# ESP8266_BREAKOUT.net
KiCad netlist of a schematic drawn in EAGLE
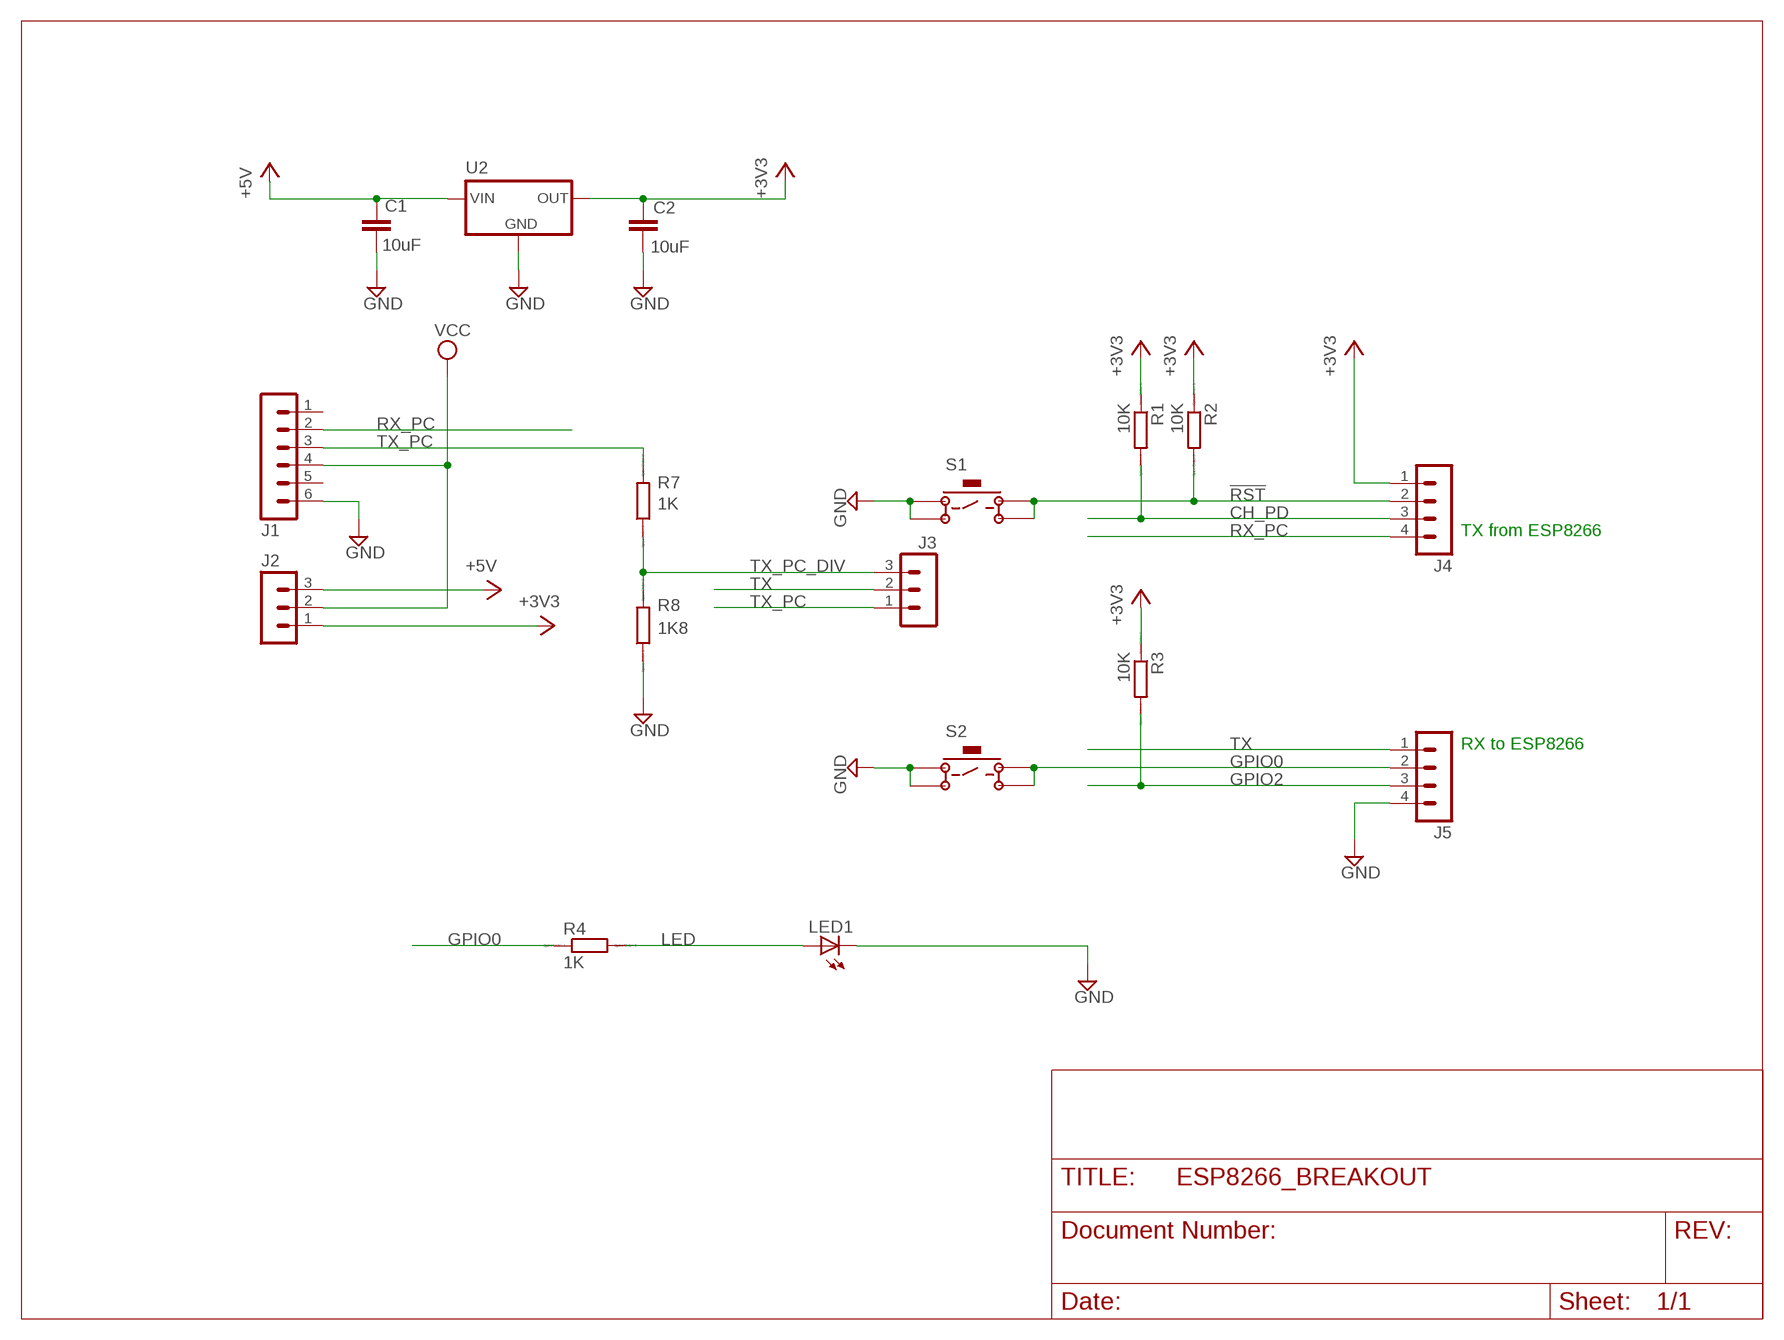
[diagram p0: schematic, sheet 1]

(export (version "E")
  (design (tool "Eeschema 10.0.6"))
  (components
    (comp (ref "C1")
      (value "10uF")
      (footprint "eagle-import:C5B2.5")
      (libsource (lib "eagle-import") (part "C5/2.5"))
    )
    (comp (ref "C2")
      (value "10uF")
      (footprint "eagle-import:C5B2.5")
      (libsource (lib "eagle-import") (part "C5/2.5"))
    )
    (comp (ref "J1")
      (value "MA06-1")
      (footprint "eagle-import:MA06-1")
      (libsource (lib "eagle-import") (part "MA06-1"))
    )
    (comp (ref "J2")
      (value "MA03-1")
      (footprint "eagle-import:MA03-1")
      (libsource (lib "eagle-import") (part "MA03-1"))
    )
    (comp (ref "J3")
      (value "MA03-1")
      (footprint "eagle-import:MA03-1")
      (libsource (lib "eagle-import") (part "MA03-1"))
    )
    (comp (ref "J4")
      (value "MA04-1")
      (footprint "eagle-import:MA04-1")
      (libsource (lib "eagle-import") (part "MA04-1"))
    )
    (comp (ref "J5")
      (value "MA04-1")
      (footprint "eagle-import:MA04-1")
      (libsource (lib "eagle-import") (part "MA04-1"))
    )
    (comp (ref "LED1")
      (value "LED5MM")
      (footprint "eagle-import:LED5MM")
      (libsource (lib "eagle-import") (part "LED5MM"))
    )
    (comp (ref "R1")
      (value "10K")
      (footprint "eagle-import:0204_7")
      (libsource (lib "eagle-import") (part "R-EU_0204_7"))
    )
    (comp (ref "R2")
      (value "10K")
      (footprint "eagle-import:0204_7")
      (libsource (lib "eagle-import") (part "R-EU_0204_7"))
    )
    (comp (ref "R3")
      (value "10K")
      (footprint "eagle-import:0204_7")
      (libsource (lib "eagle-import") (part "R-EU_0204_7"))
    )
    (comp (ref "R4")
      (value "1K")
      (footprint "eagle-import:0204_7")
      (libsource (lib "eagle-import") (part "R-EU_0204_7"))
    )
    (comp (ref "R7")
      (value "1K")
      (footprint "eagle-import:0204_7")
      (libsource (lib "eagle-import") (part "R-EU_0204_7"))
    )
    (comp (ref "R8")
      (value "1K8")
      (footprint "eagle-import:0204_7")
      (libsource (lib "eagle-import") (part "R-EU_0204_7"))
    )
    (comp (ref "S1")
      (value "1825910-6-SPST-NOPB-4P")
      (footprint "eagle-import:SW-NOPB-4")
      (libsource (lib "eagle-import") (part "1825910-6-SPST-NOPB-4P"))
    )
    (comp (ref "S2")
      (value "1825910-6-SPST-NOPB-4P")
      (footprint "eagle-import:SW-NOPB-4")
      (libsource (lib "eagle-import") (part "1825910-6-SPST-NOPB-4P"))
    )
    (comp (ref "U2")
      (value "LM1117-3V3-T0-220")
      (footprint "eagle-import:TO-220")
      (libsource (lib "eagle-import") (part "LM1117-3V3-T0-220"))
    )
  )
  (nets
    (net (code "1") (name "+3V3") (class "Default")
      (node (ref "C2") (pin "2") (pinfunction "2_2") (pintype "passive"))
      (node (ref "J2") (pin "1") (pinfunction "1_1") (pintype "passive"))
      (node (ref "J4") (pin "1") (pinfunction "1_1") (pintype "passive"))
      (node (ref "R1") (pin "1") (pinfunction "1_1") (pintype "passive"))
      (node (ref "R2") (pin "1") (pinfunction "1_1") (pintype "passive"))
      (node (ref "R3") (pin "1") (pinfunction "1_1") (pintype "passive"))
      (node (ref "U2") (pin "P$2") (pinfunction "OUT_P$2") (pintype "passive"))
    )
    (net (code "2") (name "+5V") (class "Default")
      (node (ref "C1") (pin "2") (pinfunction "2_2") (pintype "passive"))
      (node (ref "J2") (pin "3") (pinfunction "3_3") (pintype "passive"))
      (node (ref "U2") (pin "P$3") (pinfunction "IN_P$3") (pintype "input"))
    )
    (net (code "3") (name "/CH_PD") (class "Default")
      (node (ref "J4") (pin "3") (pinfunction "3_3") (pintype "passive"))
      (node (ref "R1") (pin "2") (pinfunction "2_2") (pintype "passive"))
    )
    (net (code "4") (name "/GPIO0") (class "Default")
      (node (ref "J5") (pin "2") (pinfunction "2_2") (pintype "passive"))
      (node (ref "R4") (pin "1") (pinfunction "1_1") (pintype "passive"))
      (node (ref "S2") (pin "3") (pinfunction "3_3") (pintype "bidirectional"))
      (node (ref "S2") (pin "4") (pinfunction "4_4") (pintype "bidirectional"))
    )
    (net (code "5") (name "/GPIO2") (class "Default")
      (node (ref "J5") (pin "3") (pinfunction "3_3") (pintype "passive"))
      (node (ref "R3") (pin "2") (pinfunction "2_2") (pintype "passive"))
    )
    (net (code "6") (name "/LED") (class "Default")
      (node (ref "LED1") (pin "A") (pinfunction "A_A") (pintype "passive"))
      (node (ref "R4") (pin "2") (pinfunction "2_2") (pintype "passive"))
    )
    (net (code "7") (name "/RX_PC") (class "Default")
      (node (ref "J1") (pin "2") (pinfunction "2_2") (pintype "passive"))
      (node (ref "J4") (pin "4") (pinfunction "4_4") (pintype "passive"))
    )
    (net (code "8") (name "/TX") (class "Default")
      (node (ref "J3") (pin "2") (pinfunction "2_2") (pintype "passive"))
      (node (ref "J5") (pin "1") (pinfunction "1_1") (pintype "passive"))
    )
    (net (code "9") (name "/TX_PC") (class "Default")
      (node (ref "J1") (pin "3") (pinfunction "3_3") (pintype "passive"))
      (node (ref "J3") (pin "1") (pinfunction "1_1") (pintype "passive"))
      (node (ref "R7") (pin "2") (pinfunction "2_2") (pintype "passive"))
    )
    (net (code "10") (name "/TX_PC_DIV") (class "Default")
      (node (ref "J3") (pin "3") (pinfunction "3_3") (pintype "passive"))
      (node (ref "R7") (pin "1") (pinfunction "1_1") (pintype "passive"))
      (node (ref "R8") (pin "2") (pinfunction "2_2") (pintype "passive"))
    )
    (net (code "11") (name "/~{RST}") (class "Default")
      (node (ref "J4") (pin "2") (pinfunction "2_2") (pintype "passive"))
      (node (ref "R2") (pin "2") (pinfunction "2_2") (pintype "passive"))
      (node (ref "S1") (pin "3") (pinfunction "3_3") (pintype "bidirectional"))
      (node (ref "S1") (pin "4") (pinfunction "4_4") (pintype "bidirectional"))
    )
    (net (code "12") (name "GND") (class "Default")
      (node (ref "C1") (pin "1") (pinfunction "1_1") (pintype "passive"))
      (node (ref "C2") (pin "1") (pinfunction "1_1") (pintype "passive"))
      (node (ref "J1") (pin "6") (pinfunction "6_6") (pintype "passive"))
      (node (ref "J5") (pin "4") (pinfunction "4_4") (pintype "passive"))
      (node (ref "LED1") (pin "K") (pinfunction "C_K") (pintype "passive"))
      (node (ref "R8") (pin "1") (pinfunction "1_1") (pintype "passive"))
      (node (ref "S1") (pin "1") (pinfunction "1_1") (pintype "bidirectional"))
      (node (ref "S1") (pin "2") (pinfunction "2_2") (pintype "bidirectional"))
      (node (ref "S2") (pin "1") (pinfunction "1_1") (pintype "bidirectional"))
      (node (ref "S2") (pin "2") (pinfunction "2_2") (pintype "bidirectional"))
      (node (ref "U2") (pin "P$1") (pinfunction "GND_P$1") (pintype "input"))
    )
    (net (code "13") (name "VCC") (class "Default")
      (node (ref "J1") (pin "4") (pinfunction "4_4") (pintype "passive"))
      (node (ref "J2") (pin "2") (pinfunction "2_2") (pintype "passive"))
    )
    (net (code "14") (name "unconnected-(J1-Pad1)") (class "Default")
      (node (ref "J1") (pin "1") (pinfunction "1_1") (pintype "passive"))
    )
    (net (code "15") (name "unconnected-(J1-Pad5)") (class "Default")
      (node (ref "J1") (pin "5") (pinfunction "5_5") (pintype "passive"))
    )
  )
)
